# Template_PiggyBack.net
KiCad netlist of a schematic drawn in EAGLE
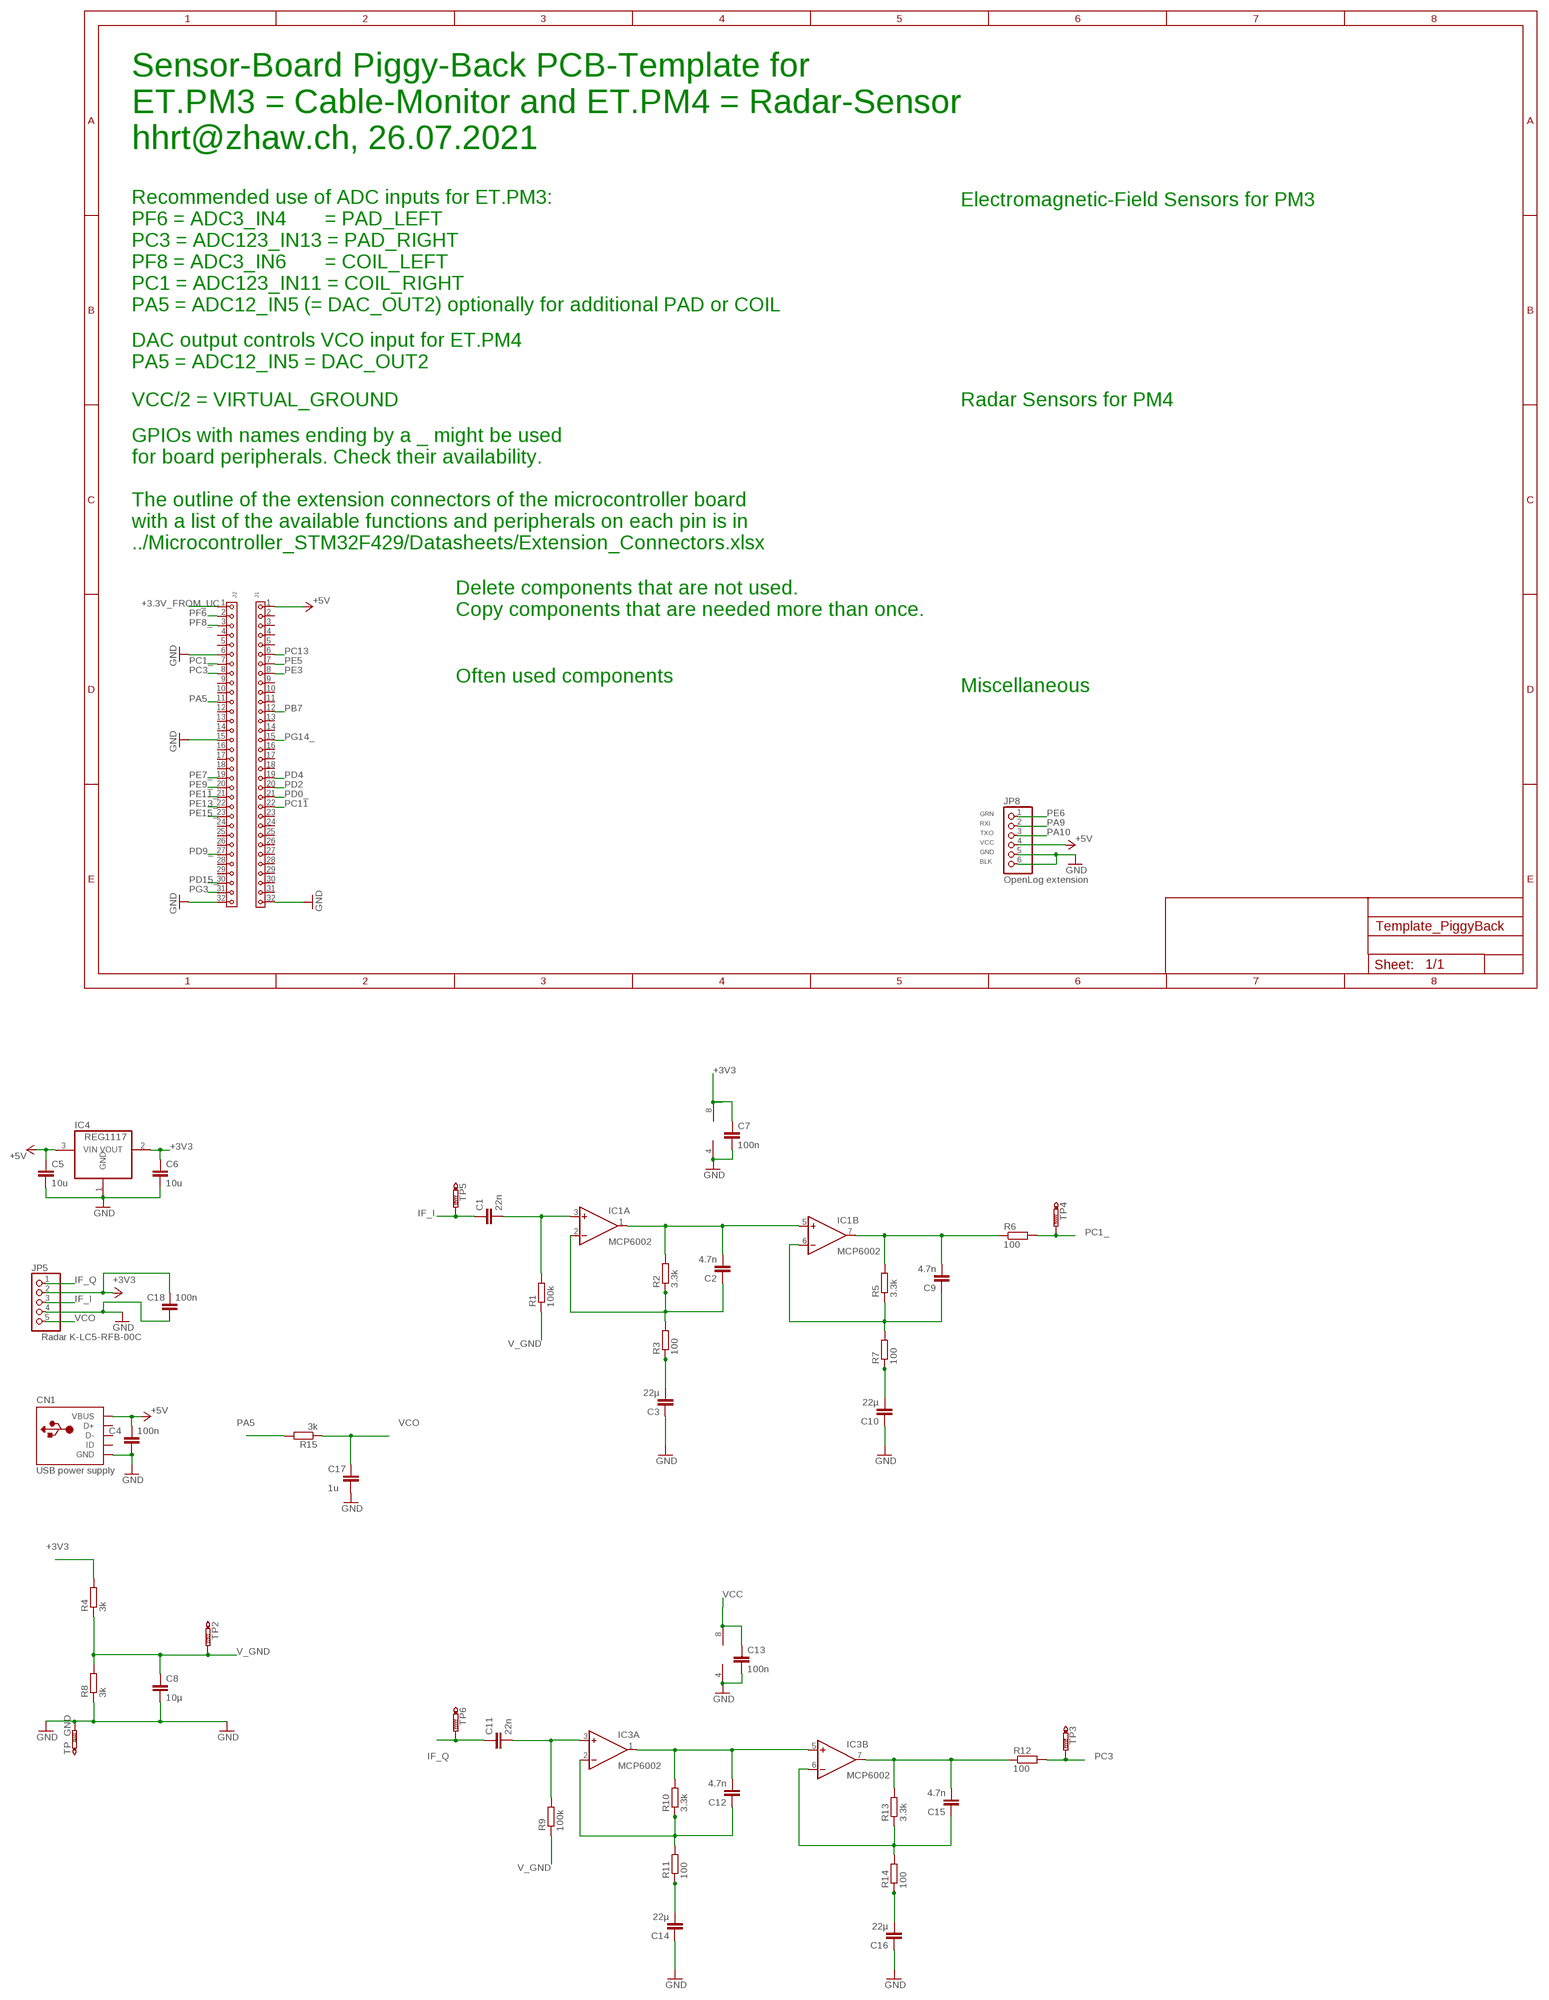
[diagram p0: schematic, sheet 1]

(export (version "E")
  (design (tool "Eeschema 10.0.6"))
  (components
    (comp (ref "C1")
      (value "22n")
      (footprint "eagle-import:C1206")
      (libsource (lib "eagle-import") (part "C-EUC1206"))
    )
    (comp (ref "C2")
      (value "4.7n")
      (footprint "eagle-import:C0805")
      (libsource (lib "eagle-import") (part "C-EUC0805"))
    )
    (comp (ref "C3")
      (value "22µ")
      (footprint "eagle-import:C0805")
      (libsource (lib "eagle-import") (part "C-EUC0805"))
    )
    (comp (ref "C4")
      (value "100n")
      (footprint "eagle-import:C0805")
      (libsource (lib "eagle-import") (part "C-EUC0805"))
    )
    (comp (ref "C5")
      (value "10u")
      (footprint "eagle-import:C0805")
      (libsource (lib "eagle-import") (part "C-EUC0805"))
    )
    (comp (ref "C6")
      (value "10u")
      (footprint "eagle-import:C0805")
      (libsource (lib "eagle-import") (part "C-EUC0805"))
    )
    (comp (ref "C7")
      (value "100n")
      (footprint "eagle-import:C0805")
      (libsource (lib "eagle-import") (part "C-EUC0805"))
    )
    (comp (ref "C8")
      (value "10µ")
      (footprint "eagle-import:C0805")
      (libsource (lib "eagle-import") (part "C-EUC0805"))
    )
    (comp (ref "C9")
      (value "4.7n")
      (footprint "eagle-import:C0805")
      (libsource (lib "eagle-import") (part "C-EUC0805"))
    )
    (comp (ref "C10")
      (value "22µ")
      (footprint "eagle-import:C0805")
      (libsource (lib "eagle-import") (part "C-EUC0805"))
    )
    (comp (ref "C11")
      (value "22n")
      (footprint "eagle-import:C1206")
      (libsource (lib "eagle-import") (part "C-EUC1206"))
    )
    (comp (ref "C12")
      (value "4.7n")
      (footprint "eagle-import:C0805")
      (libsource (lib "eagle-import") (part "C-EUC0805"))
    )
    (comp (ref "C13")
      (value "100n")
      (footprint "eagle-import:C0805")
      (libsource (lib "eagle-import") (part "C-EUC0805"))
    )
    (comp (ref "C14")
      (value "22µ")
      (footprint "eagle-import:C0805")
      (libsource (lib "eagle-import") (part "C-EUC0805"))
    )
    (comp (ref "C15")
      (value "4.7n")
      (footprint "eagle-import:C0805")
      (libsource (lib "eagle-import") (part "C-EUC0805"))
    )
    (comp (ref "C16")
      (value "22µ")
      (footprint "eagle-import:C0805")
      (libsource (lib "eagle-import") (part "C-EUC0805"))
    )
    (comp (ref "C17")
      (value "1u")
      (footprint "eagle-import:C0805")
      (libsource (lib "eagle-import") (part "C-EUC0805"))
    )
    (comp (ref "C18")
      (value "100n")
      (footprint "eagle-import:C0805")
      (libsource (lib "eagle-import") (part "C-EUC0805"))
    )
    (comp (ref "CN1")
      (value "USB power supply")
      (footprint "eagle-import:USB-MINIB")
      (libsource (lib "eagle-import") (part "USBMINIB"))
    )
    (comp (ref "IC1")
      (value "MCP6002")
      (footprint "eagle-import:SO08")
      (libsource (lib "eagle-import") (part "OPA2333D"))
    )
    (comp (ref "IC3")
      (value "MCP6002")
      (footprint "eagle-import:SO08")
      (libsource (lib "eagle-import") (part "OPA2333D"))
    )
    (comp (ref "IC4")
      (value "REG1117")
      (footprint "eagle-import:SOT223")
      (libsource (lib "eagle-import") (part "REG1117"))
    )
    (comp (ref "J1")
      (value "6130XX11821_61303211821")
      (footprint "eagle-import:61303211821")
      (libsource (lib "eagle-import") (part "6130XX11821_61303211821"))
    )
    (comp (ref "J2")
      (value "6130XX11821_61303211821")
      (footprint "eagle-import:61303211821")
      (libsource (lib "eagle-import") (part "6130XX11821_61303211821"))
    )
    (comp (ref "JP5")
      (value "Radar K-LC5-RFB-00C")
      (footprint "eagle-import:1X05")
      (libsource (lib "eagle-import") (part "PINHD-1X5"))
    )
    (comp (ref "JP8")
      (value "OpenLog extension")
      (footprint "eagle-import:1X06")
      (libsource (lib "eagle-import") (part "PINHD-1X6"))
    )
    (comp (ref "R1")
      (value "100k")
      (footprint "eagle-import:R0805")
      (libsource (lib "eagle-import") (part "R-EU_R0805"))
    )
    (comp (ref "R2")
      (value "3.3k")
      (footprint "eagle-import:R0805")
      (libsource (lib "eagle-import") (part "R-EU_R0805"))
    )
    (comp (ref "R3")
      (value "100")
      (footprint "eagle-import:R0805")
      (libsource (lib "eagle-import") (part "R-EU_R0805"))
    )
    (comp (ref "R4")
      (value "3k")
      (footprint "eagle-import:R0805")
      (libsource (lib "eagle-import") (part "R-EU_R0805"))
    )
    (comp (ref "R5")
      (value "3.3k")
      (footprint "eagle-import:R0805")
      (libsource (lib "eagle-import") (part "R-EU_R0805"))
    )
    (comp (ref "R6")
      (value "100")
      (footprint "eagle-import:R0805")
      (libsource (lib "eagle-import") (part "R-EU_R0805"))
    )
    (comp (ref "R7")
      (value "100")
      (footprint "eagle-import:R0805")
      (libsource (lib "eagle-import") (part "R-EU_R0805"))
    )
    (comp (ref "R8")
      (value "3k")
      (footprint "eagle-import:R0805")
      (libsource (lib "eagle-import") (part "R-EU_R0805"))
    )
    (comp (ref "R9")
      (value "100k")
      (footprint "eagle-import:R0805")
      (libsource (lib "eagle-import") (part "R-EU_R0805"))
    )
    (comp (ref "R10")
      (value "3.3k")
      (footprint "eagle-import:R0805")
      (libsource (lib "eagle-import") (part "R-EU_R0805"))
    )
    (comp (ref "R11")
      (value "100")
      (footprint "eagle-import:R0805")
      (libsource (lib "eagle-import") (part "R-EU_R0805"))
    )
    (comp (ref "R12")
      (value "100")
      (footprint "eagle-import:R0805")
      (libsource (lib "eagle-import") (part "R-EU_R0805"))
    )
    (comp (ref "R13")
      (value "3.3k")
      (footprint "eagle-import:R0805")
      (libsource (lib "eagle-import") (part "R-EU_R0805"))
    )
    (comp (ref "R14")
      (value "100")
      (footprint "eagle-import:R0805")
      (libsource (lib "eagle-import") (part "R-EU_R0805"))
    )
    (comp (ref "R15")
      (value "3k")
      (footprint "eagle-import:R0805")
      (libsource (lib "eagle-import") (part "R-EU_R0805"))
    )
    (comp (ref "TP2")
      (value "PTR1PAD1-17")
      (footprint "eagle-import:P1-17")
      (libsource (lib "eagle-import") (part "PTR1PAD1-17"))
    )
    (comp (ref "TP3")
      (value "PTR1PAD1-17")
      (footprint "eagle-import:P1-17")
      (libsource (lib "eagle-import") (part "PTR1PAD1-17"))
    )
    (comp (ref "TP4")
      (value "PTR1PAD1-17")
      (footprint "eagle-import:P1-17")
      (libsource (lib "eagle-import") (part "PTR1PAD1-17"))
    )
    (comp (ref "TP5")
      (value "PTR1PAD1-17")
      (footprint "eagle-import:P1-17")
      (libsource (lib "eagle-import") (part "PTR1PAD1-17"))
    )
    (comp (ref "TP6")
      (value "PTR1PAD1-17")
      (footprint "eagle-import:P1-17")
      (libsource (lib "eagle-import") (part "PTR1PAD1-17"))
    )
    (comp (ref "TP_GND")
      (value "PTR1PAD1-17")
      (footprint "eagle-import:P1-17")
      (libsource (lib "eagle-import") (part "PTR1PAD1-17"))
    )
  )
  (nets
    (net (code "1") (name "+3V3") (class "Default")
      (node (ref "C18") (pin "1") (pinfunction "1_1") (pintype "passive"))
      (node (ref "C6") (pin "1") (pinfunction "1_1") (pintype "passive"))
      (node (ref "C7") (pin "1") (pinfunction "1_1") (pintype "passive"))
      (node (ref "IC1") (pin "8") (pinfunction "V+_8") (pintype "power_in"))
      (node (ref "IC4") (pin "2") (pinfunction "VOUT_2") (pintype "output"))
      (node (ref "JP5") (pin "2") (pinfunction "2_2") (pintype "passive"))
      (node (ref "R4") (pin "2") (pinfunction "2_2") (pintype "passive"))
    )
    (net (code "2") (name "+5V") (class "Default")
      (node (ref "C4") (pin "1") (pinfunction "1_1") (pintype "passive"))
      (node (ref "C5") (pin "1") (pinfunction "1_1") (pintype "passive"))
      (node (ref "CN1") (pin "VBUS") (pinfunction "VBUS_VBUS") (pintype "power_in"))
      (node (ref "IC4") (pin "3") (pinfunction "VIN_3") (pintype "input"))
      (node (ref "J1") (pin "1") (pinfunction "1_1") (pintype "passive"))
      (node (ref "JP8") (pin "4") (pinfunction "4_4") (pintype "passive"))
    )
    (net (code "3") (name "/+3.3V_FROM_UC") (class "Default")
      (node (ref "J2") (pin "1") (pinfunction "1_1") (pintype "passive"))
    )
    (net (code "4") (name "/IF_I") (class "Default")
      (node (ref "C1") (pin "1") (pinfunction "1_1") (pintype "passive"))
      (node (ref "JP5") (pin "3") (pinfunction "3_3") (pintype "passive"))
      (node (ref "TP5") (pin "TP") (pinfunction "TP_TP") (pintype "input"))
    )
    (net (code "5") (name "/IF_Q") (class "Default")
      (node (ref "C11") (pin "1") (pinfunction "1_1") (pintype "passive"))
      (node (ref "JP5") (pin "1") (pinfunction "1_1") (pintype "passive"))
      (node (ref "TP6") (pin "TP") (pinfunction "TP_TP") (pintype "input"))
    )
    (net (code "6") (name "/PA5") (class "Default")
      (node (ref "J2") (pin "11") (pinfunction "11_11") (pintype "passive"))
      (node (ref "R15") (pin "2") (pinfunction "2_2") (pintype "passive"))
    )
    (net (code "7") (name "/PA9") (class "Default")
      (node (ref "JP8") (pin "2") (pinfunction "2_2") (pintype "passive"))
    )
    (net (code "8") (name "/PA10") (class "Default")
      (node (ref "JP8") (pin "3") (pinfunction "3_3") (pintype "passive"))
    )
    (net (code "9") (name "/PB7") (class "Default")
      (node (ref "J1") (pin "12") (pinfunction "12_12") (pintype "passive"))
    )
    (net (code "10") (name "/PC1_") (class "Default")
      (node (ref "J2") (pin "7") (pinfunction "7_7") (pintype "passive"))
      (node (ref "R6") (pin "2") (pinfunction "2_2") (pintype "passive"))
      (node (ref "TP4") (pin "TP") (pinfunction "TP_TP") (pintype "input"))
    )
    (net (code "11") (name "/PC3") (class "Default")
      (node (ref "J2") (pin "8") (pinfunction "8_8") (pintype "passive"))
      (node (ref "R12") (pin "2") (pinfunction "2_2") (pintype "passive"))
      (node (ref "TP3") (pin "TP") (pinfunction "TP_TP") (pintype "input"))
    )
    (net (code "12") (name "/PC11") (class "Default")
      (node (ref "J1") (pin "22") (pinfunction "22_22") (pintype "passive"))
    )
    (net (code "13") (name "/PC13") (class "Default")
      (node (ref "J1") (pin "6") (pinfunction "6_6") (pintype "passive"))
    )
    (net (code "14") (name "/PD0_") (class "Default")
      (node (ref "J1") (pin "21") (pinfunction "21_21") (pintype "passive"))
    )
    (net (code "15") (name "/PD2") (class "Default")
      (node (ref "J1") (pin "20") (pinfunction "20_20") (pintype "passive"))
    )
    (net (code "16") (name "/PD4") (class "Default")
      (node (ref "J1") (pin "19") (pinfunction "19_19") (pintype "passive"))
    )
    (net (code "17") (name "/PD9_") (class "Default")
      (node (ref "J2") (pin "27") (pinfunction "27_27") (pintype "passive"))
    )
    (net (code "18") (name "/PD15_") (class "Default")
      (node (ref "J2") (pin "30") (pinfunction "30_30") (pintype "passive"))
    )
    (net (code "19") (name "/PE3") (class "Default")
      (node (ref "J1") (pin "8") (pinfunction "8_8") (pintype "passive"))
    )
    (net (code "20") (name "/PE5") (class "Default")
      (node (ref "J1") (pin "7") (pinfunction "7_7") (pintype "passive"))
    )
    (net (code "21") (name "/PE6") (class "Default")
      (node (ref "JP8") (pin "1") (pinfunction "1_1") (pintype "passive"))
    )
    (net (code "22") (name "/PE7_") (class "Default")
      (node (ref "J2") (pin "19") (pinfunction "19_19") (pintype "passive"))
    )
    (net (code "23") (name "/PE9_") (class "Default")
      (node (ref "J2") (pin "20") (pinfunction "20_20") (pintype "passive"))
    )
    (net (code "24") (name "/PE11_") (class "Default")
      (node (ref "J2") (pin "21") (pinfunction "21_21") (pintype "passive"))
    )
    (net (code "25") (name "/PE13_") (class "Default")
      (node (ref "J2") (pin "22") (pinfunction "22_22") (pintype "passive"))
    )
    (net (code "26") (name "/PE15_") (class "Default")
      (node (ref "J2") (pin "23") (pinfunction "23_23") (pintype "passive"))
    )
    (net (code "27") (name "/PF6") (class "Default")
      (node (ref "J2") (pin "2") (pinfunction "2_2") (pintype "passive"))
    )
    (net (code "28") (name "/PF8_") (class "Default")
      (node (ref "J2") (pin "3") (pinfunction "3_3") (pintype "passive"))
    )
    (net (code "29") (name "/PG3") (class "Default")
      (node (ref "J2") (pin "31") (pinfunction "31_31") (pintype "passive"))
    )
    (net (code "30") (name "/PG14_") (class "Default")
      (node (ref "J1") (pin "15") (pinfunction "15_15") (pintype "passive"))
    )
    (net (code "31") (name "/VCC") (class "Default")
      (node (ref "C13") (pin "1") (pinfunction "1_1") (pintype "passive"))
      (node (ref "IC3") (pin "8") (pinfunction "V+_8") (pintype "power_in"))
    )
    (net (code "32") (name "/VCO") (class "Default")
      (node (ref "C17") (pin "1") (pinfunction "1_1") (pintype "passive"))
      (node (ref "JP5") (pin "5") (pinfunction "5_5") (pintype "passive"))
      (node (ref "R15") (pin "1") (pinfunction "1_1") (pintype "passive"))
    )
    (net (code "33") (name "/V_GND") (class "Default")
      (node (ref "C8") (pin "1") (pinfunction "1_1") (pintype "passive"))
      (node (ref "R1") (pin "1") (pinfunction "1_1") (pintype "passive"))
      (node (ref "R4") (pin "1") (pinfunction "1_1") (pintype "passive"))
      (node (ref "R8") (pin "2") (pinfunction "2_2") (pintype "passive"))
      (node (ref "R9") (pin "1") (pinfunction "1_1") (pintype "passive"))
      (node (ref "TP2") (pin "TP") (pinfunction "TP_TP") (pintype "input"))
    )
    (net (code "34") (name "GND") (class "Default")
      (node (ref "C10") (pin "1") (pinfunction "1_1") (pintype "passive"))
      (node (ref "C13") (pin "2") (pinfunction "2_2") (pintype "passive"))
      (node (ref "C14") (pin "1") (pinfunction "1_1") (pintype "passive"))
      (node (ref "C16") (pin "1") (pinfunction "1_1") (pintype "passive"))
      (node (ref "C17") (pin "2") (pinfunction "2_2") (pintype "passive"))
      (node (ref "C18") (pin "2") (pinfunction "2_2") (pintype "passive"))
      (node (ref "C3") (pin "1") (pinfunction "1_1") (pintype "passive"))
      (node (ref "C4") (pin "2") (pinfunction "2_2") (pintype "passive"))
      (node (ref "C5") (pin "2") (pinfunction "2_2") (pintype "passive"))
      (node (ref "C6") (pin "2") (pinfunction "2_2") (pintype "passive"))
      (node (ref "C7") (pin "2") (pinfunction "2_2") (pintype "passive"))
      (node (ref "C8") (pin "2") (pinfunction "2_2") (pintype "passive"))
      (node (ref "CN1") (pin "GND") (pinfunction "GND_GND") (pintype "power_in"))
      (node (ref "IC1") (pin "4") (pinfunction "V-_4") (pintype "power_in"))
      (node (ref "IC3") (pin "4") (pinfunction "V-_4") (pintype "power_in"))
      (node (ref "IC4") (pin "1") (pinfunction "GND_1") (pintype "power_in"))
      (node (ref "J1") (pin "32") (pinfunction "32_32") (pintype "passive"))
      (node (ref "J2") (pin "15") (pinfunction "15_15") (pintype "passive"))
      (node (ref "J2") (pin "32") (pinfunction "32_32") (pintype "passive"))
      (node (ref "J2") (pin "6") (pinfunction "6_6") (pintype "passive"))
      (node (ref "JP5") (pin "4") (pinfunction "4_4") (pintype "passive"))
      (node (ref "JP8") (pin "5") (pinfunction "5_5") (pintype "passive"))
      (node (ref "JP8") (pin "6") (pinfunction "6_6") (pintype "passive"))
      (node (ref "R8") (pin "1") (pinfunction "1_1") (pintype "passive"))
      (node (ref "TP_GND") (pin "TP") (pinfunction "TP_TP") (pintype "input"))
    )
    (net (code "35") (name "Net-(C3-Pad2)") (class "Default")
      (node (ref "C3") (pin "2") (pinfunction "2_2") (pintype "passive"))
      (node (ref "R3") (pin "1") (pinfunction "1_1") (pintype "passive"))
    )
    (net (code "36") (name "Net-(C10-Pad2)") (class "Default")
      (node (ref "C10") (pin "2") (pinfunction "2_2") (pintype "passive"))
      (node (ref "R7") (pin "1") (pinfunction "1_1") (pintype "passive"))
    )
    (net (code "37") (name "Net-(C14-Pad2)") (class "Default")
      (node (ref "C14") (pin "2") (pinfunction "2_2") (pintype "passive"))
      (node (ref "R11") (pin "1") (pinfunction "1_1") (pintype "passive"))
    )
    (net (code "38") (name "Net-(C16-Pad2)") (class "Default")
      (node (ref "C16") (pin "2") (pinfunction "2_2") (pintype "passive"))
      (node (ref "R14") (pin "1") (pinfunction "1_1") (pintype "passive"))
    )
    (net (code "39") (name "Net-(IC1A-+IN)") (class "Default")
      (node (ref "C1") (pin "2") (pinfunction "2_2") (pintype "passive"))
      (node (ref "IC1") (pin "3") (pinfunction "+IN_3") (pintype "input"))
      (node (ref "R1") (pin "2") (pinfunction "2_2") (pintype "passive"))
    )
    (net (code "40") (name "Net-(IC1A--IN)") (class "Default")
      (node (ref "C2") (pin "1") (pinfunction "1_1") (pintype "passive"))
      (node (ref "IC1") (pin "2") (pinfunction "-IN_2") (pintype "input"))
      (node (ref "R2") (pin "1") (pinfunction "1_1") (pintype "passive"))
      (node (ref "R3") (pin "2") (pinfunction "2_2") (pintype "passive"))
    )
    (net (code "41") (name "Net-(IC1A-OUT)") (class "Default")
      (node (ref "C2") (pin "2") (pinfunction "2_2") (pintype "passive"))
      (node (ref "IC1") (pin "1") (pinfunction "OUT_1") (pintype "output"))
      (node (ref "IC1") (pin "5") (pinfunction "+IN_5") (pintype "input"))
      (node (ref "R2") (pin "2") (pinfunction "2_2") (pintype "passive"))
    )
    (net (code "42") (name "Net-(IC1B--IN)") (class "Default")
      (node (ref "C9") (pin "1") (pinfunction "1_1") (pintype "passive"))
      (node (ref "IC1") (pin "6") (pinfunction "-IN_6") (pintype "input"))
      (node (ref "R5") (pin "1") (pinfunction "1_1") (pintype "passive"))
      (node (ref "R7") (pin "2") (pinfunction "2_2") (pintype "passive"))
    )
    (net (code "43") (name "Net-(IC1B-OUT)") (class "Default")
      (node (ref "C9") (pin "2") (pinfunction "2_2") (pintype "passive"))
      (node (ref "IC1") (pin "7") (pinfunction "OUT_7") (pintype "output"))
      (node (ref "R5") (pin "2") (pinfunction "2_2") (pintype "passive"))
      (node (ref "R6") (pin "1") (pinfunction "1_1") (pintype "passive"))
    )
    (net (code "44") (name "Net-(IC3A-+IN)") (class "Default")
      (node (ref "C11") (pin "2") (pinfunction "2_2") (pintype "passive"))
      (node (ref "IC3") (pin "3") (pinfunction "+IN_3") (pintype "input"))
      (node (ref "R9") (pin "2") (pinfunction "2_2") (pintype "passive"))
    )
    (net (code "45") (name "Net-(IC3A--IN)") (class "Default")
      (node (ref "C12") (pin "1") (pinfunction "1_1") (pintype "passive"))
      (node (ref "IC3") (pin "2") (pinfunction "-IN_2") (pintype "input"))
      (node (ref "R10") (pin "1") (pinfunction "1_1") (pintype "passive"))
      (node (ref "R11") (pin "2") (pinfunction "2_2") (pintype "passive"))
    )
    (net (code "46") (name "Net-(IC3A-OUT)") (class "Default")
      (node (ref "C12") (pin "2") (pinfunction "2_2") (pintype "passive"))
      (node (ref "IC3") (pin "1") (pinfunction "OUT_1") (pintype "output"))
      (node (ref "IC3") (pin "5") (pinfunction "+IN_5") (pintype "input"))
      (node (ref "R10") (pin "2") (pinfunction "2_2") (pintype "passive"))
    )
    (net (code "47") (name "Net-(IC3B--IN)") (class "Default")
      (node (ref "C15") (pin "1") (pinfunction "1_1") (pintype "passive"))
      (node (ref "IC3") (pin "6") (pinfunction "-IN_6") (pintype "input"))
      (node (ref "R13") (pin "1") (pinfunction "1_1") (pintype "passive"))
      (node (ref "R14") (pin "2") (pinfunction "2_2") (pintype "passive"))
    )
    (net (code "48") (name "Net-(IC3B-OUT)") (class "Default")
      (node (ref "C15") (pin "2") (pinfunction "2_2") (pintype "passive"))
      (node (ref "IC3") (pin "7") (pinfunction "OUT_7") (pintype "output"))
      (node (ref "R12") (pin "1") (pinfunction "1_1") (pintype "passive"))
      (node (ref "R13") (pin "2") (pinfunction "2_2") (pintype "passive"))
    )
    (net (code "49") (name "unconnected-(CN1-PadD+)") (class "Default")
      (node (ref "CN1") (pin "D+") (pinfunction "D+_D+") (pintype "bidirectional"))
    )
    (net (code "50") (name "unconnected-(CN1-PadD-)") (class "Default")
      (node (ref "CN1") (pin "D-") (pinfunction "D-_D-") (pintype "bidirectional"))
    )
    (net (code "51") (name "unconnected-(CN1-PadID)") (class "Default")
      (node (ref "CN1") (pin "ID") (pinfunction "ID_ID") (pintype "bidirectional"))
    )
    (net (code "52") (name "unconnected-(J1-Pad2)") (class "Default")
      (node (ref "J1") (pin "2") (pinfunction "2_2") (pintype "passive"))
    )
    (net (code "53") (name "unconnected-(J1-Pad3)") (class "Default")
      (node (ref "J1") (pin "3") (pinfunction "3_3") (pintype "passive"))
    )
    (net (code "54") (name "unconnected-(J1-Pad4)") (class "Default")
      (node (ref "J1") (pin "4") (pinfunction "4_4") (pintype "passive"))
    )
    (net (code "55") (name "unconnected-(J1-Pad5)") (class "Default")
      (node (ref "J1") (pin "5") (pinfunction "5_5") (pintype "passive"))
    )
    (net (code "56") (name "unconnected-(J1-Pad9)") (class "Default")
      (node (ref "J1") (pin "9") (pinfunction "9_9") (pintype "passive"))
    )
    (net (code "57") (name "unconnected-(J1-Pad10)") (class "Default")
      (node (ref "J1") (pin "10") (pinfunction "10_10") (pintype "passive"))
    )
    (net (code "58") (name "unconnected-(J1-Pad11)") (class "Default")
      (node (ref "J1") (pin "11") (pinfunction "11_11") (pintype "passive"))
    )
    (net (code "59") (name "unconnected-(J1-Pad13)") (class "Default")
      (node (ref "J1") (pin "13") (pinfunction "13_13") (pintype "passive"))
    )
    (net (code "60") (name "unconnected-(J1-Pad14)") (class "Default")
      (node (ref "J1") (pin "14") (pinfunction "14_14") (pintype "passive"))
    )
    (net (code "61") (name "unconnected-(J1-Pad16)") (class "Default")
      (node (ref "J1") (pin "16") (pinfunction "16_16") (pintype "passive"))
    )
    (net (code "62") (name "unconnected-(J1-Pad17)") (class "Default")
      (node (ref "J1") (pin "17") (pinfunction "17_17") (pintype "passive"))
    )
    (net (code "63") (name "unconnected-(J1-Pad18)") (class "Default")
      (node (ref "J1") (pin "18") (pinfunction "18_18") (pintype "passive"))
    )
    (net (code "64") (name "unconnected-(J1-Pad23)") (class "Default")
      (node (ref "J1") (pin "23") (pinfunction "23_23") (pintype "passive"))
    )
    (net (code "65") (name "unconnected-(J1-Pad24)") (class "Default")
      (node (ref "J1") (pin "24") (pinfunction "24_24") (pintype "passive"))
    )
    (net (code "66") (name "unconnected-(J1-Pad25)") (class "Default")
      (node (ref "J1") (pin "25") (pinfunction "25_25") (pintype "passive"))
    )
    (net (code "67") (name "unconnected-(J1-Pad26)") (class "Default")
      (node (ref "J1") (pin "26") (pinfunction "26_26") (pintype "passive"))
    )
    (net (code "68") (name "unconnected-(J1-Pad27)") (class "Default")
      (node (ref "J1") (pin "27") (pinfunction "27_27") (pintype "passive"))
    )
    (net (code "69") (name "unconnected-(J1-Pad28)") (class "Default")
      (node (ref "J1") (pin "28") (pinfunction "28_28") (pintype "passive"))
    )
    (net (code "70") (name "unconnected-(J1-Pad29)") (class "Default")
      (node (ref "J1") (pin "29") (pinfunction "29_29") (pintype "passive"))
    )
    (net (code "71") (name "unconnected-(J1-Pad30)") (class "Default")
      (node (ref "J1") (pin "30") (pinfunction "30_30") (pintype "passive"))
    )
    (net (code "72") (name "unconnected-(J1-Pad31)") (class "Default")
      (node (ref "J1") (pin "31") (pinfunction "31_31") (pintype "passive"))
    )
    (net (code "73") (name "unconnected-(J2-Pad4)") (class "Default")
      (node (ref "J2") (pin "4") (pinfunction "4_4") (pintype "passive"))
    )
    (net (code "74") (name "unconnected-(J2-Pad5)") (class "Default")
      (node (ref "J2") (pin "5") (pinfunction "5_5") (pintype "passive"))
    )
    (net (code "75") (name "unconnected-(J2-Pad9)") (class "Default")
      (node (ref "J2") (pin "9") (pinfunction "9_9") (pintype "passive"))
    )
    (net (code "76") (name "unconnected-(J2-Pad10)") (class "Default")
      (node (ref "J2") (pin "10") (pinfunction "10_10") (pintype "passive"))
    )
    (net (code "77") (name "unconnected-(J2-Pad12)") (class "Default")
      (node (ref "J2") (pin "12") (pinfunction "12_12") (pintype "passive"))
    )
    (net (code "78") (name "unconnected-(J2-Pad13)") (class "Default")
      (node (ref "J2") (pin "13") (pinfunction "13_13") (pintype "passive"))
    )
    (net (code "79") (name "unconnected-(J2-Pad14)") (class "Default")
      (node (ref "J2") (pin "14") (pinfunction "14_14") (pintype "passive"))
    )
    (net (code "80") (name "unconnected-(J2-Pad16)") (class "Default")
      (node (ref "J2") (pin "16") (pinfunction "16_16") (pintype "passive"))
    )
    (net (code "81") (name "unconnected-(J2-Pad17)") (class "Default")
      (node (ref "J2") (pin "17") (pinfunction "17_17") (pintype "passive"))
    )
    (net (code "82") (name "unconnected-(J2-Pad18)") (class "Default")
      (node (ref "J2") (pin "18") (pinfunction "18_18") (pintype "passive"))
    )
    (net (code "83") (name "unconnected-(J2-Pad24)") (class "Default")
      (node (ref "J2") (pin "24") (pinfunction "24_24") (pintype "passive"))
    )
    (net (code "84") (name "unconnected-(J2-Pad25)") (class "Default")
      (node (ref "J2") (pin "25") (pinfunction "25_25") (pintype "passive"))
    )
    (net (code "85") (name "unconnected-(J2-Pad26)") (class "Default")
      (node (ref "J2") (pin "26") (pinfunction "26_26") (pintype "passive"))
    )
    (net (code "86") (name "unconnected-(J2-Pad28)") (class "Default")
      (node (ref "J2") (pin "28") (pinfunction "28_28") (pintype "passive"))
    )
    (net (code "87") (name "unconnected-(J2-Pad29)") (class "Default")
      (node (ref "J2") (pin "29") (pinfunction "29_29") (pintype "passive"))
    )
  )
)
